# sensor_v2.net
KiCad netlist of a schematic drawn in EAGLE
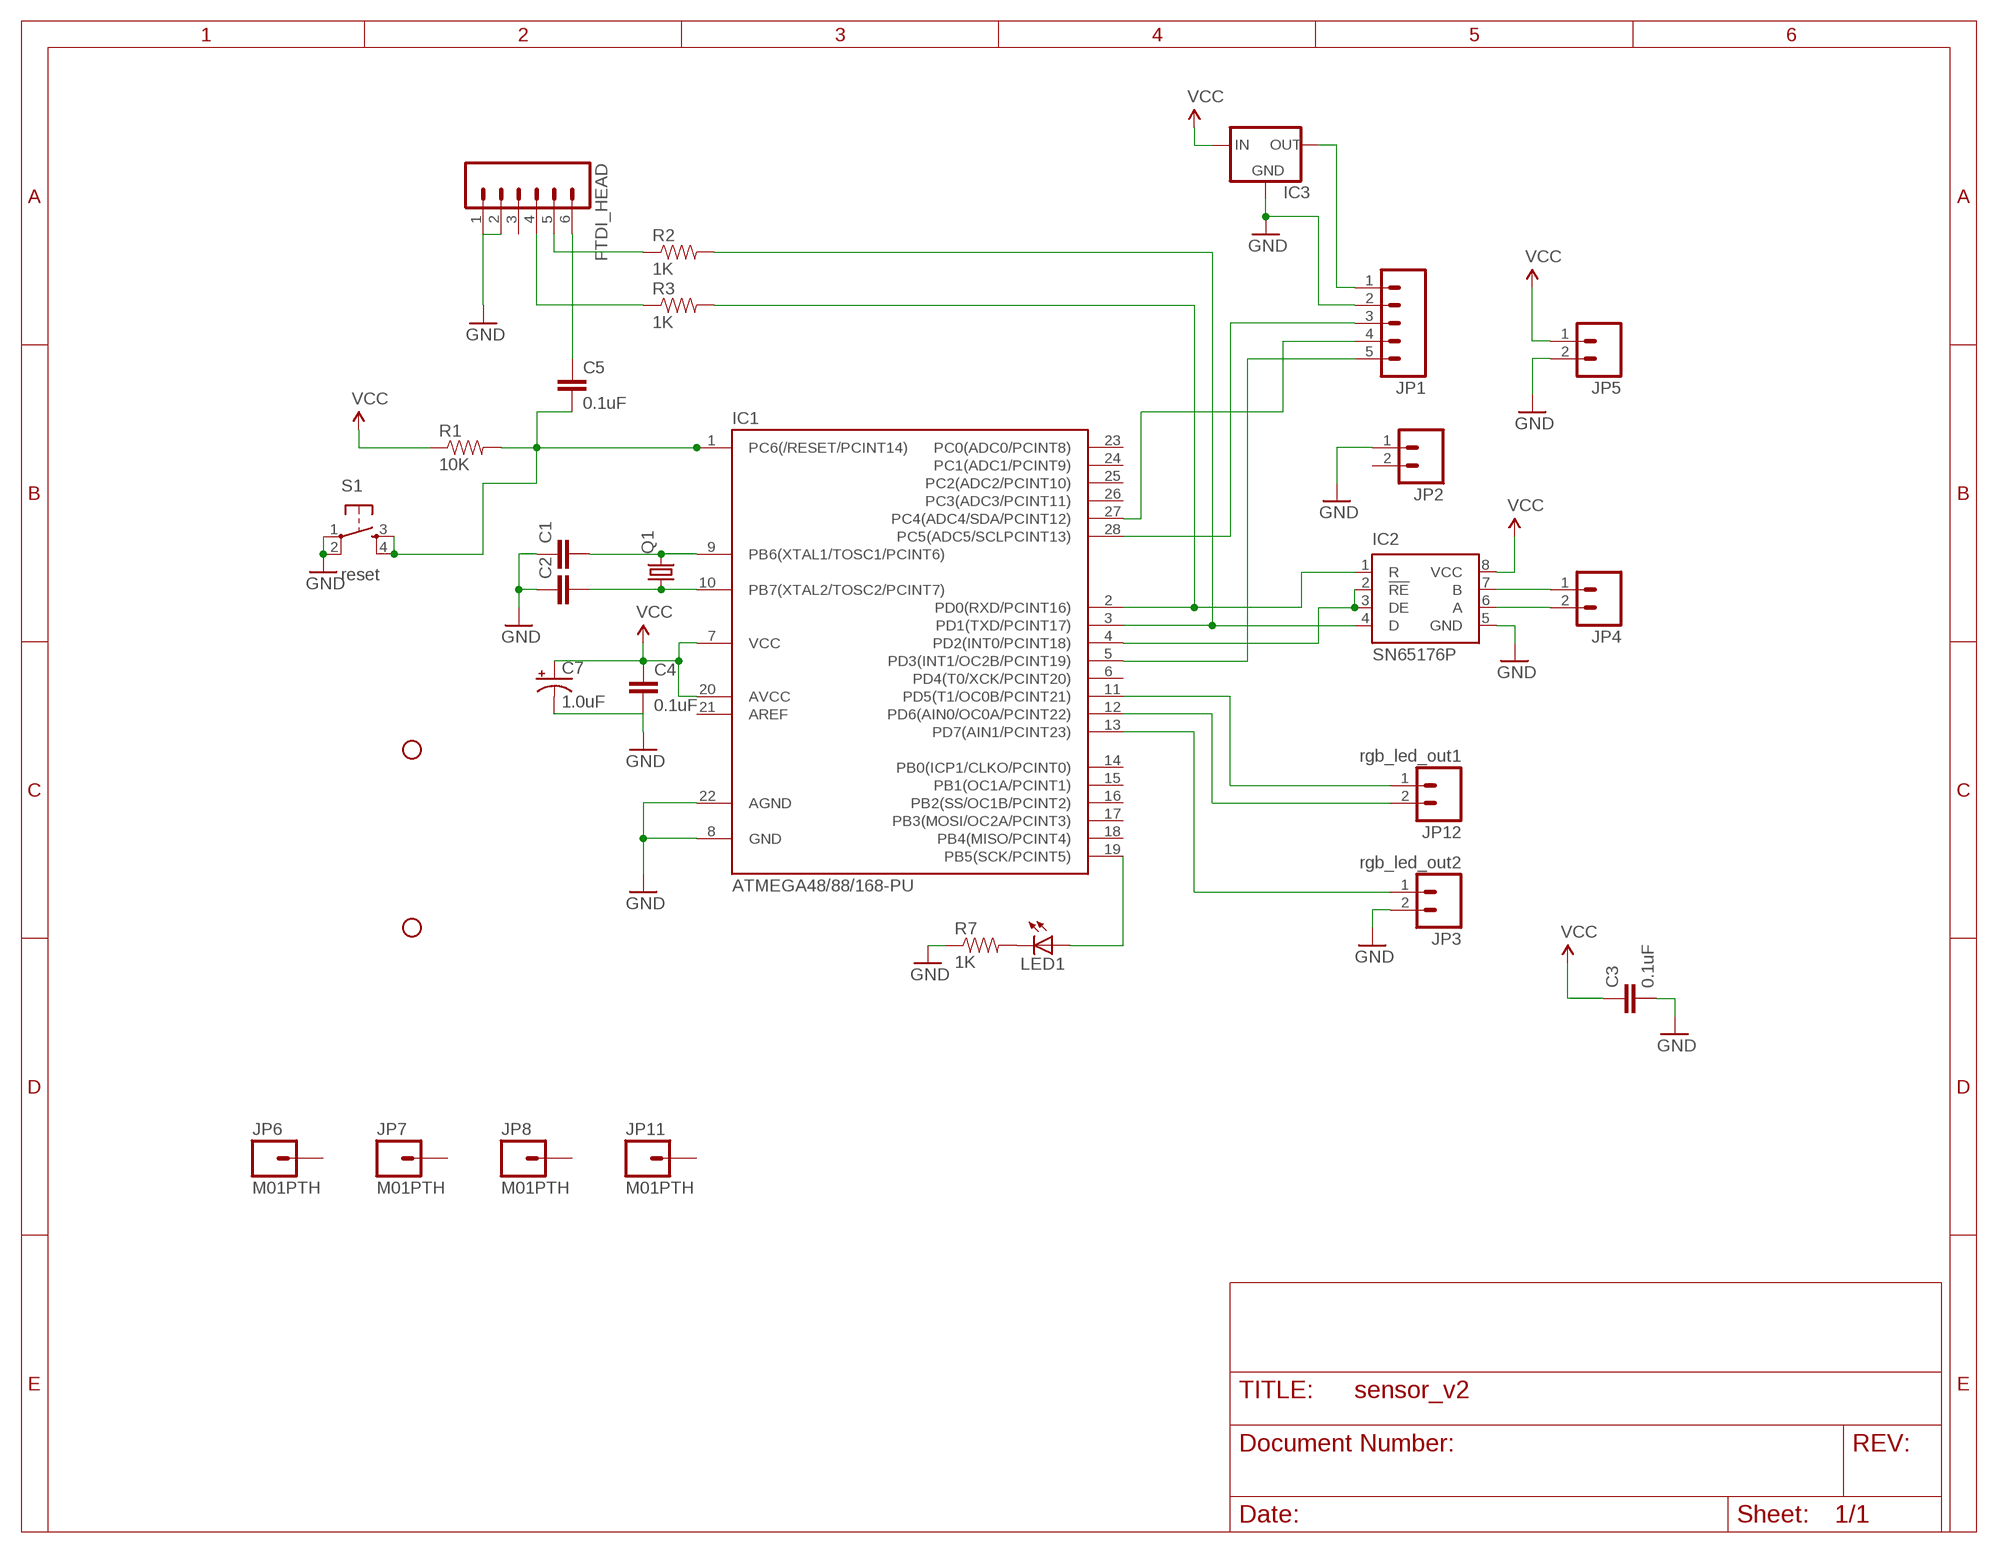
[diagram p0: schematic, sheet 1]

(export (version "E")
  (design (tool "Eeschema 10.0.6"))
  (components
    (comp (ref "C1")
      (value "CAPPTH")
      (footprint "eagle-import:CAP-PTH-SMALL")
      (libsource (lib "eagle-import") (part "CAPPTH"))
    )
    (comp (ref "C2")
      (value "CAPPTH")
      (footprint "eagle-import:CAP-PTH-SMALL")
      (libsource (lib "eagle-import") (part "CAPPTH"))
    )
    (comp (ref "C3")
      (value "0.1uF")
      (footprint "eagle-import:CAP-PTH-SMALL")
      (libsource (lib "eagle-import") (part "CAPPTH"))
    )
    (comp (ref "C4")
      (value "0.1uF")
      (footprint "eagle-import:CAP-PTH-SMALL")
      (libsource (lib "eagle-import") (part "CAPPTH"))
    )
    (comp (ref "C5")
      (value "0.1uF")
      (footprint "eagle-import:CAP-PTH-SMALL")
      (libsource (lib "eagle-import") (part "CAPPTH"))
    )
    (comp (ref "C7")
      (value "1.0uF")
      (footprint "eagle-import:CPOL-RADIAL-10UF-25V")
      (libsource (lib "eagle-import") (part "CAP_POLPTH2"))
    )
    (comp (ref "FTDI_HEAD")
      (value "M06LOCK_LONGPADS")
      (footprint "eagle-import:1X06_LOCK_LONGPADS")
      (libsource (lib "eagle-import") (part "M06LOCK_LONGPADS"))
    )
    (comp (ref "IC1")
      (value "ATMEGA48/88/168-PU")
      (footprint "eagle-import:DIL28-3")
      (libsource (lib "eagle-import") (part "ATMEGA48/88/168-PU"))
    )
    (comp (ref "IC2")
      (value "SN65176P")
      (footprint "eagle-import:DIL08")
      (libsource (lib "eagle-import") (part "SN65176P"))
    )
    (comp (ref "IC3")
      (value "78LXX")
      (footprint "eagle-import:78LXX")
      (libsource (lib "eagle-import") (part "78LXX"))
    )
    (comp (ref "JP1")
      (value "M05LOCK_LONGPADS")
      (footprint "eagle-import:1X05_LOCK_LONGPADS")
      (libsource (lib "eagle-import") (part "M05LOCK_LONGPADS"))
    )
    (comp (ref "JP2")
      (value "M02LOCK_LONGPADS")
      (footprint "eagle-import:1X02_LOCK_LONGPADS")
      (libsource (lib "eagle-import") (part "M02LOCK_LONGPADS"))
    )
    (comp (ref "JP3")
      (value "rgb_led_out2")
      (footprint "eagle-import:1X02")
      (libsource (lib "eagle-import") (part "M02PTH"))
    )
    (comp (ref "JP4")
      (value "M02PTH")
      (footprint "eagle-import:1X02")
      (libsource (lib "eagle-import") (part "M02PTH"))
    )
    (comp (ref "JP5")
      (value "M02PTH")
      (footprint "eagle-import:1X02")
      (libsource (lib "eagle-import") (part "M02PTH"))
    )
    (comp (ref "JP6")
      (value "M01PTH")
      (footprint "eagle-import:1X01")
      (libsource (lib "eagle-import") (part "M01PTH"))
    )
    (comp (ref "JP7")
      (value "M01PTH")
      (footprint "eagle-import:1X01")
      (libsource (lib "eagle-import") (part "M01PTH"))
    )
    (comp (ref "JP8")
      (value "M01PTH")
      (footprint "eagle-import:1X01")
      (libsource (lib "eagle-import") (part "M01PTH"))
    )
    (comp (ref "JP9")
      (value "STAND-OFF")
      (footprint "eagle-import:STAND-OFF")
      (libsource (lib "eagle-import") (part "STAND-OFF"))
    )
    (comp (ref "JP10")
      (value "STAND-OFF")
      (footprint "eagle-import:STAND-OFF")
      (libsource (lib "eagle-import") (part "STAND-OFF"))
    )
    (comp (ref "JP11")
      (value "M01PTH")
      (footprint "eagle-import:1X01")
      (libsource (lib "eagle-import") (part "M01PTH"))
    )
    (comp (ref "JP12")
      (value "rgb_led_out1")
      (footprint "eagle-import:1X02")
      (libsource (lib "eagle-import") (part "M02PTH"))
    )
    (comp (ref "LED1")
      (value "LED5MM")
      (footprint "eagle-import:LED5MM")
      (libsource (lib "eagle-import") (part "LED5MM"))
    )
    (comp (ref "Q1")
      (value "CRYSTALHC49U-V")
      (footprint "eagle-import:HC49U-V")
      (libsource (lib "eagle-import") (part "CRYSTALHC49U-V"))
    )
    (comp (ref "R1")
      (value "10K")
      (footprint "eagle-import:AXIAL-0.3")
      (libsource (lib "eagle-import") (part "RESISTORPTH1"))
    )
    (comp (ref "R2")
      (value "1K")
      (footprint "eagle-import:AXIAL-0.3")
      (libsource (lib "eagle-import") (part "RESISTORPTH1"))
    )
    (comp (ref "R3")
      (value "1K")
      (footprint "eagle-import:AXIAL-0.3")
      (libsource (lib "eagle-import") (part "RESISTORPTH1"))
    )
    (comp (ref "R7")
      (value "1K")
      (footprint "eagle-import:AXIAL-0.3")
      (libsource (lib "eagle-import") (part "RESISTORPTH1"))
    )
    (comp (ref "S1")
      (value "reset")
      (footprint "eagle-import:TACTILE-PTH")
      (libsource (lib "eagle-import") (part "TAC_SWITCHPTH"))
    )
  )
  (nets
    (net (code "1") (name "GND") (class "Default")
      (node (ref "C1") (pin "1") (pinfunction "1_1") (pintype "passive"))
      (node (ref "C2") (pin "1") (pinfunction "1_1") (pintype "passive"))
      (node (ref "C3") (pin "2") (pinfunction "2_2") (pintype "passive"))
      (node (ref "C4") (pin "2") (pinfunction "2_2") (pintype "passive"))
      (node (ref "C7") (pin "2") (pinfunction "-_2") (pintype "passive"))
      (node (ref "FTDI_HEAD") (pin "1") (pinfunction "1_1") (pintype "passive"))
      (node (ref "FTDI_HEAD") (pin "2") (pinfunction "2_2") (pintype "passive"))
      (node (ref "IC1") (pin "22") (pinfunction "AGND_22") (pintype "power_in"))
      (node (ref "IC1") (pin "8") (pinfunction "GND_8") (pintype "power_in"))
      (node (ref "IC2") (pin "5") (pinfunction "GND_5") (pintype "input"))
      (node (ref "IC3") (pin "GND") (pinfunction "GND_GND") (pintype "input"))
      (node (ref "JP1") (pin "2") (pinfunction "2_2") (pintype "passive"))
      (node (ref "JP2") (pin "1") (pinfunction "1_1") (pintype "passive"))
      (node (ref "JP3") (pin "2") (pinfunction "2_2") (pintype "passive"))
      (node (ref "JP5") (pin "2") (pinfunction "2_2") (pintype "passive"))
      (node (ref "R7") (pin "P$1") (pinfunction "1_P$1") (pintype "passive"))
      (node (ref "S1") (pin "1") (pinfunction "1_1") (pintype "passive"))
      (node (ref "S1") (pin "2") (pinfunction "2_2") (pintype "passive"))
    )
    (net (code "2") (name "Net-(C5-Pad1)") (class "Default")
      (node (ref "C5") (pin "1") (pinfunction "1_1") (pintype "passive"))
      (node (ref "FTDI_HEAD") (pin "6") (pinfunction "6_6") (pintype "passive"))
    )
    (net (code "3") (name "Net-(IC1-PB5(SCK{slash}PCINT5))") (class "Default")
      (node (ref "IC1") (pin "19") (pinfunction "PB5(SCK/PCINT5)_19") (pintype "bidirectional"))
      (node (ref "LED1") (pin "A") (pinfunction "A_A") (pintype "passive"))
    )
    (net (code "4") (name "Net-(IC1-PB6(XTAL1{slash}TOSC1{slash}PCINT6))") (class "Default")
      (node (ref "C1") (pin "2") (pinfunction "2_2") (pintype "passive"))
      (node (ref "IC1") (pin "9") (pinfunction "PB6(XTAL1/TOSC1/PCINT6)_9") (pintype "bidirectional"))
      (node (ref "Q1") (pin "2") (pinfunction "2_2") (pintype "passive"))
    )
    (net (code "5") (name "Net-(IC1-PB7(XTAL2{slash}TOSC2{slash}PCINT7))") (class "Default")
      (node (ref "C2") (pin "2") (pinfunction "2_2") (pintype "passive"))
      (node (ref "IC1") (pin "10") (pinfunction "PB7(XTAL2/TOSC2/PCINT7)_10") (pintype "bidirectional"))
      (node (ref "Q1") (pin "1") (pinfunction "1_1") (pintype "passive"))
    )
    (net (code "6") (name "Net-(IC1-PC4(ADC4{slash}SDA{slash}PCINT12))") (class "Default")
      (node (ref "IC1") (pin "27") (pinfunction "PC4(ADC4/SDA/PCINT12)_27") (pintype "bidirectional"))
      (node (ref "JP1") (pin "4") (pinfunction "4_4") (pintype "passive"))
    )
    (net (code "7") (name "Net-(IC1-PC5(ADC5{slash}SCLPCINT13))") (class "Default")
      (node (ref "IC1") (pin "28") (pinfunction "PC5(ADC5/SCLPCINT13)_28") (pintype "bidirectional"))
      (node (ref "JP1") (pin "3") (pinfunction "3_3") (pintype "passive"))
    )
    (net (code "8") (name "Net-(IC1-PC6({slash}RESET{slash}PCINT14))") (class "Default")
      (node (ref "C5") (pin "2") (pinfunction "2_2") (pintype "passive"))
      (node (ref "IC1") (pin "1") (pinfunction "PC6(/RESET/PCINT14)_1") (pintype "bidirectional"))
      (node (ref "R1") (pin "P$2") (pinfunction "2_P$2") (pintype "passive"))
      (node (ref "S1") (pin "3") (pinfunction "3_3") (pintype "passive"))
      (node (ref "S1") (pin "4") (pinfunction "4_4") (pintype "passive"))
    )
    (net (code "9") (name "Net-(IC1-PD0(RXD{slash}PCINT16))") (class "Default")
      (node (ref "IC1") (pin "2") (pinfunction "PD0(RXD/PCINT16)_2") (pintype "bidirectional"))
      (node (ref "IC2") (pin "1") (pinfunction "R_1") (pintype "input"))
      (node (ref "R3") (pin "P$2") (pinfunction "2_P$2") (pintype "passive"))
    )
    (net (code "10") (name "Net-(IC1-PD1(TXD{slash}PCINT17))") (class "Default")
      (node (ref "IC1") (pin "3") (pinfunction "PD1(TXD/PCINT17)_3") (pintype "bidirectional"))
      (node (ref "IC2") (pin "4") (pinfunction "D_4") (pintype "input"))
      (node (ref "R2") (pin "P$2") (pinfunction "2_P$2") (pintype "passive"))
    )
    (net (code "11") (name "Net-(IC1-PD2(INT0{slash}PCINT18))") (class "Default")
      (node (ref "IC1") (pin "4") (pinfunction "PD2(INT0/PCINT18)_4") (pintype "bidirectional"))
      (node (ref "IC2") (pin "2") (pinfunction "~{RE}_2") (pintype "input"))
      (node (ref "IC2") (pin "3") (pinfunction "DE_3") (pintype "input"))
    )
    (net (code "12") (name "Net-(IC1-PD3(INT1{slash}OC2B{slash}PCINT19))") (class "Default")
      (node (ref "IC1") (pin "5") (pinfunction "PD3(INT1/OC2B/PCINT19)_5") (pintype "bidirectional"))
      (node (ref "JP1") (pin "5") (pinfunction "5_5") (pintype "passive"))
    )
    (net (code "13") (name "Net-(IC1-PD5(T1{slash}OC0B{slash}PCINT21))") (class "Default")
      (node (ref "IC1") (pin "11") (pinfunction "PD5(T1/OC0B/PCINT21)_11") (pintype "bidirectional"))
      (node (ref "JP12") (pin "1") (pinfunction "1_1") (pintype "passive"))
    )
    (net (code "14") (name "Net-(IC1-PD6(AIN0{slash}OC0A{slash}PCINT22))") (class "Default")
      (node (ref "IC1") (pin "12") (pinfunction "PD6(AIN0/OC0A/PCINT22)_12") (pintype "bidirectional"))
      (node (ref "JP12") (pin "2") (pinfunction "2_2") (pintype "passive"))
    )
    (net (code "15") (name "Net-(IC1-PD7(AIN1{slash}PCINT23))") (class "Default")
      (node (ref "IC1") (pin "13") (pinfunction "PD7(AIN1/PCINT23)_13") (pintype "bidirectional"))
      (node (ref "JP3") (pin "1") (pinfunction "1_1") (pintype "passive"))
    )
    (net (code "16") (name "Net-(IC2-A)") (class "Default")
      (node (ref "IC2") (pin "6") (pinfunction "A_6") (pintype "input"))
      (node (ref "JP4") (pin "2") (pinfunction "2_2") (pintype "passive"))
    )
    (net (code "17") (name "Net-(IC2-B)") (class "Default")
      (node (ref "IC2") (pin "7") (pinfunction "B_7") (pintype "input"))
      (node (ref "JP4") (pin "1") (pinfunction "1_1") (pintype "passive"))
    )
    (net (code "18") (name "Net-(IC3-PadOUT)") (class "Default")
      (node (ref "IC3") (pin "OUT") (pinfunction "OUT_OUT") (pintype "passive"))
      (node (ref "JP1") (pin "1") (pinfunction "1_1") (pintype "passive"))
    )
    (net (code "19") (name "Net-(LED1-C)") (class "Default")
      (node (ref "LED1") (pin "K") (pinfunction "C_K") (pintype "passive"))
      (node (ref "R7") (pin "P$2") (pinfunction "2_P$2") (pintype "passive"))
    )
    (net (code "20") (name "Net-(R2-1)") (class "Default")
      (node (ref "FTDI_HEAD") (pin "5") (pinfunction "5_5") (pintype "passive"))
      (node (ref "R2") (pin "P$1") (pinfunction "1_P$1") (pintype "passive"))
    )
    (net (code "21") (name "Net-(R3-1)") (class "Default")
      (node (ref "FTDI_HEAD") (pin "4") (pinfunction "4_4") (pintype "passive"))
      (node (ref "R3") (pin "P$1") (pinfunction "1_P$1") (pintype "passive"))
    )
    (net (code "22") (name "VCC") (class "Default")
      (node (ref "C3") (pin "1") (pinfunction "1_1") (pintype "passive"))
      (node (ref "C4") (pin "1") (pinfunction "1_1") (pintype "passive"))
      (node (ref "C7") (pin "1") (pinfunction "+_1") (pintype "passive"))
      (node (ref "IC1") (pin "20") (pinfunction "AVCC_20") (pintype "passive"))
      (node (ref "IC1") (pin "7") (pinfunction "VCC_7") (pintype "power_in"))
      (node (ref "IC2") (pin "8") (pinfunction "VCC_8") (pintype "input"))
      (node (ref "IC3") (pin "IN") (pinfunction "IN_IN") (pintype "input"))
      (node (ref "JP5") (pin "1") (pinfunction "1_1") (pintype "passive"))
      (node (ref "R1") (pin "P$1") (pinfunction "1_P$1") (pintype "passive"))
    )
    (net (code "23") (name "unconnected-(FTDI_HEAD-Pad3)") (class "Default")
      (node (ref "FTDI_HEAD") (pin "3") (pinfunction "3_3") (pintype "passive"))
    )
    (net (code "24") (name "unconnected-(IC1-AREF-Pad21)") (class "Default")
      (node (ref "IC1") (pin "21") (pinfunction "AREF_21") (pintype "passive"))
    )
    (net (code "25") (name "unconnected-(IC1-PB0(ICP1{slash}CLKO{slash}PCINT0)-Pad14)") (class "Default")
      (node (ref "IC1") (pin "14") (pinfunction "PB0(ICP1/CLKO/PCINT0)_14") (pintype "bidirectional"))
    )
    (net (code "26") (name "unconnected-(IC1-PB1(OC1A{slash}PCINT1)-Pad15)") (class "Default")
      (node (ref "IC1") (pin "15") (pinfunction "PB1(OC1A/PCINT1)_15") (pintype "bidirectional"))
    )
    (net (code "27") (name "unconnected-(IC1-PB2(SS{slash}OC1B{slash}PCINT2)-Pad16)") (class "Default")
      (node (ref "IC1") (pin "16") (pinfunction "PB2(SS/OC1B/PCINT2)_16") (pintype "bidirectional"))
    )
    (net (code "28") (name "unconnected-(IC1-PB3(MOSI{slash}OC2A{slash}PCINT3)-Pad17)") (class "Default")
      (node (ref "IC1") (pin "17") (pinfunction "PB3(MOSI/OC2A/PCINT3)_17") (pintype "bidirectional"))
    )
    (net (code "29") (name "unconnected-(IC1-PB4(MISO{slash}PCINT4)-Pad18)") (class "Default")
      (node (ref "IC1") (pin "18") (pinfunction "PB4(MISO/PCINT4)_18") (pintype "bidirectional"))
    )
    (net (code "30") (name "unconnected-(IC1-PC0(ADC0{slash}PCINT8)-Pad23)") (class "Default")
      (node (ref "IC1") (pin "23") (pinfunction "PC0(ADC0/PCINT8)_23") (pintype "bidirectional"))
    )
    (net (code "31") (name "unconnected-(IC1-PC1(ADC1{slash}PCINT9)-Pad24)") (class "Default")
      (node (ref "IC1") (pin "24") (pinfunction "PC1(ADC1/PCINT9)_24") (pintype "bidirectional"))
    )
    (net (code "32") (name "unconnected-(IC1-PC2(ADC2{slash}PCINT10)-Pad25)") (class "Default")
      (node (ref "IC1") (pin "25") (pinfunction "PC2(ADC2/PCINT10)_25") (pintype "bidirectional"))
    )
    (net (code "33") (name "unconnected-(IC1-PC3(ADC3{slash}PCINT11)-Pad26)") (class "Default")
      (node (ref "IC1") (pin "26") (pinfunction "PC3(ADC3/PCINT11)_26") (pintype "bidirectional"))
    )
    (net (code "34") (name "unconnected-(IC1-PD4(T0{slash}XCK{slash}PCINT20)-Pad6)") (class "Default")
      (node (ref "IC1") (pin "6") (pinfunction "PD4(T0/XCK/PCINT20)_6") (pintype "bidirectional"))
    )
    (net (code "35") (name "unconnected-(JP2-Pad2)") (class "Default")
      (node (ref "JP2") (pin "2") (pinfunction "2_2") (pintype "passive"))
    )
    (net (code "36") (name "unconnected-(JP6-Pad1)") (class "Default")
      (node (ref "JP6") (pin "1") (pinfunction "1_1") (pintype "passive"))
    )
    (net (code "37") (name "unconnected-(JP7-Pad1)") (class "Default")
      (node (ref "JP7") (pin "1") (pinfunction "1_1") (pintype "passive"))
    )
    (net (code "38") (name "unconnected-(JP8-Pad1)") (class "Default")
      (node (ref "JP8") (pin "1") (pinfunction "1_1") (pintype "passive"))
    )
    (net (code "39") (name "unconnected-(JP11-Pad1)") (class "Default")
      (node (ref "JP11") (pin "1") (pinfunction "1_1") (pintype "passive"))
    )
  )
)
